# BLE_--_HM-10_ATtiny85_Combo_--_v03.net
KiCad netlist of a schematic drawn in EAGLE
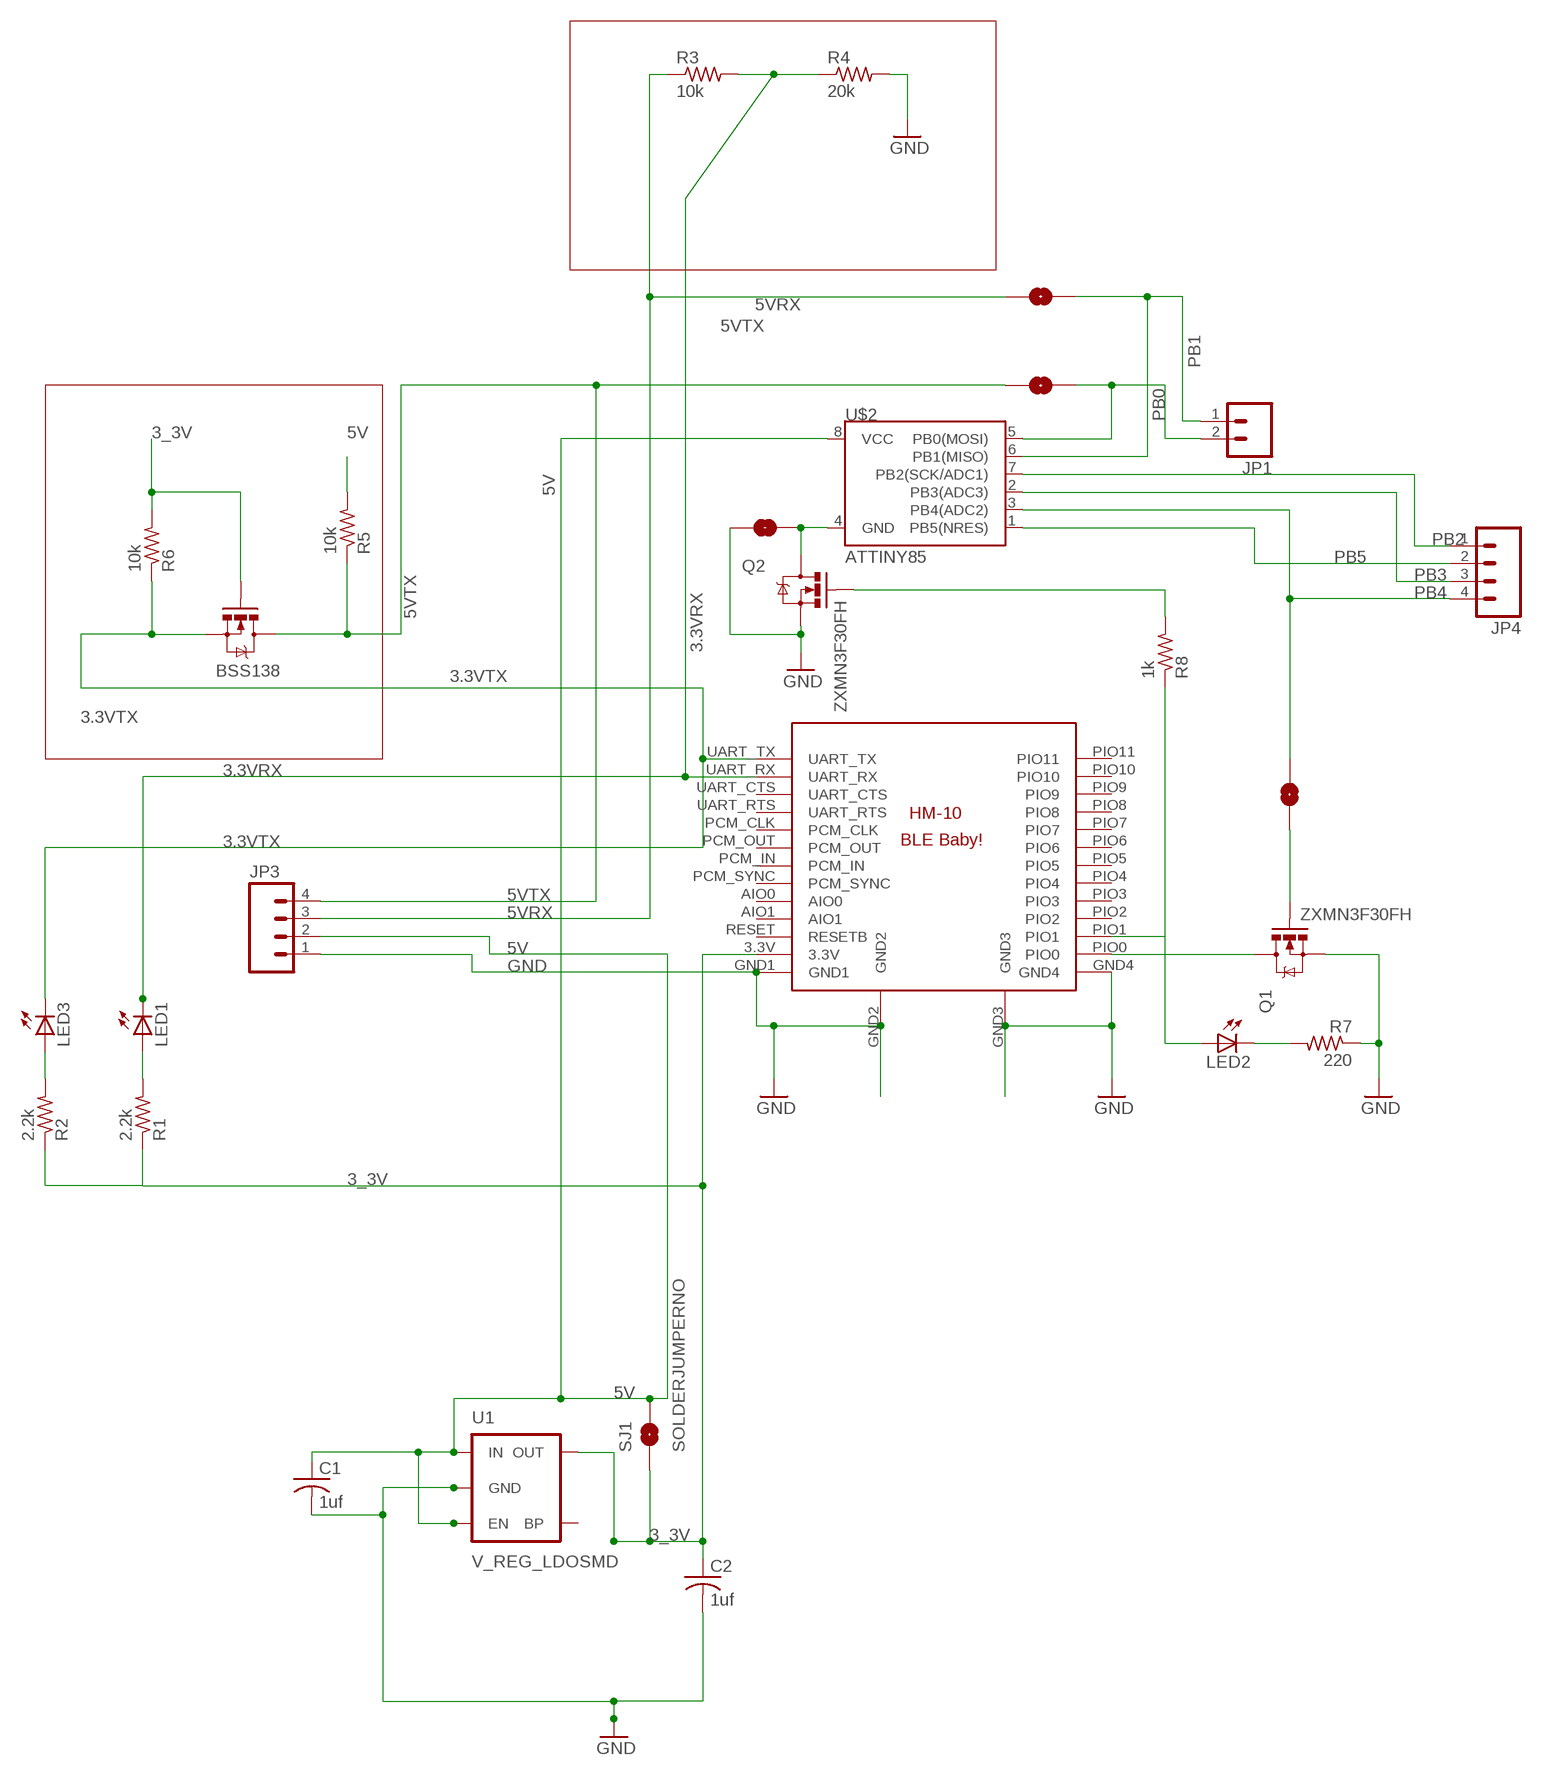
[diagram p0: schematic, sheet 1]

(export (version "E")
  (design (tool "Eeschema 10.0.6"))
  (components
    (comp (ref "BSS138")
      (value "MOSFET-NCHANNELSMD")
      (footprint "eagle-import:SOT23-3")
      (libsource (lib "eagle-import") (part "MOSFET-NCHANNELSMD"))
    )
    (comp (ref "C1")
      (value "1uf")
      (footprint "eagle-import:C0402")
      (libsource (lib "eagle-import") (part "C-USC0402"))
    )
    (comp (ref "C2")
      (value "1uf")
      (footprint "eagle-import:C0402")
      (libsource (lib "eagle-import") (part "C-USC0402"))
    )
    (comp (ref "JP1")
      (value "M02PTH")
      (footprint "eagle-import:1X02")
      (libsource (lib "eagle-import") (part "M02PTH"))
    )
    (comp (ref "JP3")
      (value "M04PTH")
      (footprint "eagle-import:1X04")
      (libsource (lib "eagle-import") (part "M04PTH"))
    )
    (comp (ref "JP4")
      (value "M04PTH")
      (footprint "eagle-import:1X04")
      (libsource (lib "eagle-import") (part "M04PTH"))
    )
    (comp (ref "LED1")
      (value "LED0603")
      (footprint "eagle-import:LED-0603")
      (libsource (lib "eagle-import") (part "LED0603"))
    )
    (comp (ref "LED2")
      (value "LED0603")
      (footprint "eagle-import:LED-0603")
      (libsource (lib "eagle-import") (part "LED0603"))
    )
    (comp (ref "LED3")
      (value "LED0603")
      (footprint "eagle-import:LED-0603")
      (libsource (lib "eagle-import") (part "LED0603"))
    )
    (comp (ref "Q1")
      (value "ZXMN3F30FH")
      (footprint "eagle-import:SOT23-3")
      (libsource (lib "eagle-import") (part "MOSFET-NCHANNELSMD"))
    )
    (comp (ref "Q2")
      (value "ZXMN3F30FH")
      (footprint "eagle-import:SOT23-3")
      (libsource (lib "eagle-import") (part "MOSFET-NCHANNELSMD"))
    )
    (comp (ref "R1")
      (value "2.2k")
      (footprint "eagle-import:R0402")
      (libsource (lib "eagle-import") (part "R-US_R0402"))
    )
    (comp (ref "R2")
      (value "2.2k")
      (footprint "eagle-import:R0402")
      (libsource (lib "eagle-import") (part "R-US_R0402"))
    )
    (comp (ref "R3")
      (value "10k")
      (footprint "eagle-import:R0402")
      (libsource (lib "eagle-import") (part "R-US_R0402"))
    )
    (comp (ref "R4")
      (value "20k")
      (footprint "eagle-import:R0402")
      (libsource (lib "eagle-import") (part "R-US_R0402"))
    )
    (comp (ref "R5")
      (value "10k")
      (footprint "eagle-import:R0402")
      (libsource (lib "eagle-import") (part "R-US_R0402"))
    )
    (comp (ref "R6")
      (value "10k")
      (footprint "eagle-import:R0402")
      (libsource (lib "eagle-import") (part "R-US_R0402"))
    )
    (comp (ref "R7")
      (value "220")
      (footprint "eagle-import:R0402")
      (libsource (lib "eagle-import") (part "R-US_R0402"))
    )
    (comp (ref "R8")
      (value "1k")
      (footprint "eagle-import:R0402")
      (libsource (lib "eagle-import") (part "R-US_R0402"))
    )
    (comp (ref "SJ1")
      (value "SOLDERJUMPERNO")
      (footprint "eagle-import:SJ_2S-NO")
      (libsource (lib "eagle-import") (part "SOLDERJUMPERNO"))
    )
    (comp (ref "SJ2")
      (value "SOLDERJUMPERNO")
      (footprint "eagle-import:SJ_2S-NO")
      (libsource (lib "eagle-import") (part "SOLDERJUMPERNO"))
    )
    (comp (ref "SJ3")
      (value "SOLDERJUMPERNO")
      (footprint "eagle-import:SJ_2S-NO")
      (libsource (lib "eagle-import") (part "SOLDERJUMPERNO"))
    )
    (comp (ref "SJ4")
      (value "SOLDERJUMPERNO")
      (footprint "eagle-import:SJ_2S-NO")
      (libsource (lib "eagle-import") (part "SOLDERJUMPERNO"))
    )
    (comp (ref "SJ5")
      (value "SOLDERJUMPERNO")
      (footprint "eagle-import:SJ_2S-NO")
      (libsource (lib "eagle-import") (part "SOLDERJUMPERNO"))
    )
    (comp (ref "U$1")
      (value "BLE-HM10_NO_SPI")
      (footprint "eagle-import:BLE-HM10_NO_SPI")
      (libsource (lib "eagle-import") (part "BLE-HM10_NO_SPI"))
    )
    (comp (ref "U$2")
      (value "ATTINY85")
      (footprint "eagle-import:SO08-EIAJ")
      (libsource (lib "eagle-import") (part "ATTINY45"))
    )
    (comp (ref "U1")
      (value "V_REG_LDOSMD")
      (footprint "eagle-import:SOT23-5")
      (libsource (lib "eagle-import") (part "V_REG_LDOSMD"))
    )
  )
  (nets
    (net (code "1") (name "/3.3VRX") (class "Default")
      (node (ref "LED1") (pin "C") (pinfunction "C_C") (pintype "passive"))
      (node (ref "R3") (pin "2") (pinfunction "2_2") (pintype "passive"))
      (node (ref "R4") (pin "1") (pinfunction "1_1") (pintype "passive"))
      (node (ref "U$1") (pin "UART_RX") (pinfunction "UART_RX_UART_RX") (pintype "bidirectional"))
    )
    (net (code "2") (name "/3.3VTX") (class "Default")
      (node (ref "BSS138") (pin "2") (pinfunction "S_2") (pintype "passive"))
      (node (ref "LED3") (pin "C") (pinfunction "C_C") (pintype "passive"))
      (node (ref "R6") (pin "1") (pinfunction "1_1") (pintype "passive"))
      (node (ref "U$1") (pin "UART_TX") (pinfunction "UART_TX_UART_TX") (pintype "bidirectional"))
    )
    (net (code "3") (name "/3_3V") (class "Default")
      (node (ref "BSS138") (pin "1") (pinfunction "G_1") (pintype "passive"))
      (node (ref "C2") (pin "1") (pinfunction "1_1") (pintype "passive"))
      (node (ref "R1") (pin "1") (pinfunction "1_1") (pintype "passive"))
      (node (ref "R2") (pin "1") (pinfunction "1_1") (pintype "passive"))
      (node (ref "R6") (pin "2") (pinfunction "2_2") (pintype "passive"))
      (node (ref "SJ1") (pin "1") (pinfunction "1_1") (pintype "passive"))
      (node (ref "U$1") (pin "3.3V") (pinfunction "3.3V_3.3V") (pintype "bidirectional"))
      (node (ref "U1") (pin "5") (pinfunction "OUT_5") (pintype "passive"))
    )
    (net (code "4") (name "/5V") (class "Default")
      (node (ref "C1") (pin "1") (pinfunction "1_1") (pintype "passive"))
      (node (ref "JP3") (pin "2") (pinfunction "2_2") (pintype "passive"))
      (node (ref "R5") (pin "2") (pinfunction "2_2") (pintype "passive"))
      (node (ref "SJ1") (pin "2") (pinfunction "2_2") (pintype "passive"))
      (node (ref "U$2") (pin "8") (pinfunction "VCC_8") (pintype "bidirectional"))
      (node (ref "U1") (pin "1") (pinfunction "IN_1") (pintype "input"))
      (node (ref "U1") (pin "3") (pinfunction "EN_3") (pintype "input"))
    )
    (net (code "5") (name "/5VRX") (class "Default")
      (node (ref "JP3") (pin "3") (pinfunction "3_3") (pintype "passive"))
      (node (ref "R3") (pin "1") (pinfunction "1_1") (pintype "passive"))
      (node (ref "SJ3") (pin "2") (pinfunction "2_2") (pintype "passive"))
    )
    (net (code "6") (name "/5VTX") (class "Default")
      (node (ref "BSS138") (pin "3") (pinfunction "D_3") (pintype "passive"))
      (node (ref "JP3") (pin "4") (pinfunction "4_4") (pintype "passive"))
      (node (ref "R5") (pin "1") (pinfunction "1_1") (pintype "passive"))
      (node (ref "SJ2") (pin "2") (pinfunction "2_2") (pintype "passive"))
    )
    (net (code "7") (name "/PB0") (class "Default")
      (node (ref "JP1") (pin "2") (pinfunction "2_2") (pintype "passive"))
      (node (ref "SJ2") (pin "1") (pinfunction "1_1") (pintype "passive"))
      (node (ref "U$2") (pin "5") (pinfunction "PB0(MOSI)_5") (pintype "bidirectional"))
    )
    (net (code "8") (name "/PB1") (class "Default")
      (node (ref "JP1") (pin "1") (pinfunction "1_1") (pintype "passive"))
      (node (ref "SJ3") (pin "1") (pinfunction "1_1") (pintype "passive"))
      (node (ref "U$2") (pin "6") (pinfunction "PB1(MISO)_6") (pintype "bidirectional"))
    )
    (net (code "9") (name "/PB2") (class "Default")
      (node (ref "JP4") (pin "1") (pinfunction "1_1") (pintype "passive"))
      (node (ref "U$2") (pin "7") (pinfunction "PB2(SCK/ADC1)_7") (pintype "bidirectional"))
    )
    (net (code "10") (name "/PB3") (class "Default")
      (node (ref "JP4") (pin "3") (pinfunction "3_3") (pintype "passive"))
      (node (ref "U$2") (pin "2") (pinfunction "PB3(ADC3)_2") (pintype "bidirectional"))
    )
    (net (code "11") (name "/PB4") (class "Default")
      (node (ref "JP4") (pin "4") (pinfunction "4_4") (pintype "passive"))
      (node (ref "SJ4") (pin "1") (pinfunction "1_1") (pintype "passive"))
      (node (ref "U$2") (pin "3") (pinfunction "PB4(ADC2)_3") (pintype "bidirectional"))
    )
    (net (code "12") (name "/PB5") (class "Default")
      (node (ref "JP4") (pin "2") (pinfunction "2_2") (pintype "passive"))
      (node (ref "U$2") (pin "1") (pinfunction "PB5(NRES)_1") (pintype "bidirectional"))
    )
    (net (code "13") (name "GND") (class "Default")
      (node (ref "C1") (pin "2") (pinfunction "2_2") (pintype "passive"))
      (node (ref "C2") (pin "2") (pinfunction "2_2") (pintype "passive"))
      (node (ref "JP3") (pin "1") (pinfunction "1_1") (pintype "passive"))
      (node (ref "Q1") (pin "2") (pinfunction "S_2") (pintype "passive"))
      (node (ref "Q2") (pin "2") (pinfunction "S_2") (pintype "passive"))
      (node (ref "R4") (pin "2") (pinfunction "2_2") (pintype "passive"))
      (node (ref "R7") (pin "1") (pinfunction "1_1") (pintype "passive"))
      (node (ref "SJ5") (pin "1") (pinfunction "1_1") (pintype "passive"))
      (node (ref "U$1") (pin "GND1") (pinfunction "GND1_GND1") (pintype "bidirectional"))
      (node (ref "U$1") (pin "GND2") (pinfunction "GND2_GND2") (pintype "bidirectional"))
      (node (ref "U$1") (pin "GND3") (pinfunction "GND3_GND3") (pintype "bidirectional"))
      (node (ref "U$1") (pin "GND4") (pinfunction "GND4_GND4") (pintype "bidirectional"))
      (node (ref "U1") (pin "2") (pinfunction "GND_2") (pintype "input"))
    )
    (net (code "14") (name "Net-(LED1-PadA)") (class "Default")
      (node (ref "LED1") (pin "A") (pinfunction "A_A") (pintype "passive"))
      (node (ref "R1") (pin "2") (pinfunction "2_2") (pintype "passive"))
    )
    (net (code "15") (name "Net-(LED2-PadA)") (class "Default")
      (node (ref "LED2") (pin "A") (pinfunction "A_A") (pintype "passive"))
      (node (ref "R8") (pin "1") (pinfunction "1_1") (pintype "passive"))
      (node (ref "U$1") (pin "PIO1") (pinfunction "PIO1_PIO1") (pintype "bidirectional"))
    )
    (net (code "16") (name "Net-(LED2-PadC)") (class "Default")
      (node (ref "LED2") (pin "C") (pinfunction "C_C") (pintype "passive"))
      (node (ref "R7") (pin "2") (pinfunction "2_2") (pintype "passive"))
    )
    (net (code "17") (name "Net-(LED3-PadA)") (class "Default")
      (node (ref "LED3") (pin "A") (pinfunction "A_A") (pintype "passive"))
      (node (ref "R2") (pin "2") (pinfunction "2_2") (pintype "passive"))
    )
    (net (code "18") (name "Net-(Q1-D)") (class "Default")
      (node (ref "Q1") (pin "3") (pinfunction "D_3") (pintype "passive"))
      (node (ref "U$1") (pin "PIO0") (pinfunction "PIO0_PIO0") (pintype "bidirectional"))
    )
    (net (code "19") (name "Net-(Q1-G)") (class "Default")
      (node (ref "Q1") (pin "1") (pinfunction "G_1") (pintype "passive"))
      (node (ref "SJ4") (pin "2") (pinfunction "2_2") (pintype "passive"))
    )
    (net (code "20") (name "Net-(Q2-D)") (class "Default")
      (node (ref "Q2") (pin "3") (pinfunction "D_3") (pintype "passive"))
      (node (ref "SJ5") (pin "2") (pinfunction "2_2") (pintype "passive"))
      (node (ref "U$2") (pin "4") (pinfunction "GND_4") (pintype "bidirectional"))
    )
    (net (code "21") (name "Net-(Q2-G)") (class "Default")
      (node (ref "Q2") (pin "1") (pinfunction "G_1") (pintype "passive"))
      (node (ref "R8") (pin "2") (pinfunction "2_2") (pintype "passive"))
    )
    (net (code "22") (name "unconnected-(U$1-PadAIO0)") (class "Default")
      (node (ref "U$1") (pin "AIO0") (pinfunction "AIO0_AIO0") (pintype "bidirectional"))
    )
    (net (code "23") (name "unconnected-(U$1-PadAIO1)") (class "Default")
      (node (ref "U$1") (pin "AIO1") (pinfunction "AIO1_AIO1") (pintype "bidirectional"))
    )
    (net (code "24") (name "unconnected-(U$1-PadPCM_CLK)") (class "Default")
      (node (ref "U$1") (pin "PCM_CLK") (pinfunction "PCM_CLK_PCM_CLK") (pintype "bidirectional"))
    )
    (net (code "25") (name "unconnected-(U$1-PadPCM_IN)") (class "Default")
      (node (ref "U$1") (pin "PCM_IN") (pinfunction "PCM_IN_PCM_IN") (pintype "bidirectional"))
    )
    (net (code "26") (name "unconnected-(U$1-PadPCM_OUT)") (class "Default")
      (node (ref "U$1") (pin "PCM_OUT") (pinfunction "PCM_OUT_PCM_OUT") (pintype "bidirectional"))
    )
    (net (code "27") (name "unconnected-(U$1-PadPCM_SYNC)") (class "Default")
      (node (ref "U$1") (pin "PCM_SYNC") (pinfunction "PCM_SYNC_PCM_SYNC") (pintype "bidirectional"))
    )
    (net (code "28") (name "unconnected-(U$1-PadPIO2)") (class "Default")
      (node (ref "U$1") (pin "PIO2") (pinfunction "PIO2_PIO2") (pintype "bidirectional"))
    )
    (net (code "29") (name "unconnected-(U$1-PadPIO3)") (class "Default")
      (node (ref "U$1") (pin "PIO3") (pinfunction "PIO3_PIO3") (pintype "bidirectional"))
    )
    (net (code "30") (name "unconnected-(U$1-PadPIO4)") (class "Default")
      (node (ref "U$1") (pin "PIO4") (pinfunction "PIO4_PIO4") (pintype "bidirectional"))
    )
    (net (code "31") (name "unconnected-(U$1-PadPIO5)") (class "Default")
      (node (ref "U$1") (pin "PIO5") (pinfunction "PIO5_PIO5") (pintype "bidirectional"))
    )
    (net (code "32") (name "unconnected-(U$1-PadPIO6)") (class "Default")
      (node (ref "U$1") (pin "PIO6") (pinfunction "PIO6_PIO6") (pintype "bidirectional"))
    )
    (net (code "33") (name "unconnected-(U$1-PadPIO7)") (class "Default")
      (node (ref "U$1") (pin "PIO7") (pinfunction "PIO7_PIO7") (pintype "bidirectional"))
    )
    (net (code "34") (name "unconnected-(U$1-PadPIO8)") (class "Default")
      (node (ref "U$1") (pin "PIO8") (pinfunction "PIO8_PIO8") (pintype "bidirectional"))
    )
    (net (code "35") (name "unconnected-(U$1-PadPIO9)") (class "Default")
      (node (ref "U$1") (pin "PIO9") (pinfunction "PIO9_PIO9") (pintype "bidirectional"))
    )
    (net (code "36") (name "unconnected-(U$1-PadPIO10)") (class "Default")
      (node (ref "U$1") (pin "PIO10") (pinfunction "PIO10_PIO10") (pintype "bidirectional"))
    )
    (net (code "37") (name "unconnected-(U$1-PadPIO11)") (class "Default")
      (node (ref "U$1") (pin "PIO11") (pinfunction "PIO11_PIO11") (pintype "bidirectional"))
    )
    (net (code "38") (name "unconnected-(U$1-PadUART_CTS)") (class "Default")
      (node (ref "U$1") (pin "UART_CTS") (pinfunction "UART_CTS_UART_CTS") (pintype "bidirectional"))
    )
    (net (code "39") (name "unconnected-(U$1-PadUART_RTS)") (class "Default")
      (node (ref "U$1") (pin "UART_RTS") (pinfunction "UART_RTS_UART_RTS") (pintype "bidirectional"))
    )
    (net (code "40") (name "unconnected-(U$1-RESETB-PadRESET)") (class "Default")
      (node (ref "U$1") (pin "RESET") (pinfunction "RESETB_RESET") (pintype "bidirectional"))
    )
    (net (code "41") (name "unconnected-(U1-BP-Pad4)") (class "Default")
      (node (ref "U1") (pin "4") (pinfunction "BP_4") (pintype "input"))
    )
  )
)
